# SubBoard_V1.net
KiCad netlist of a schematic drawn in EAGLE
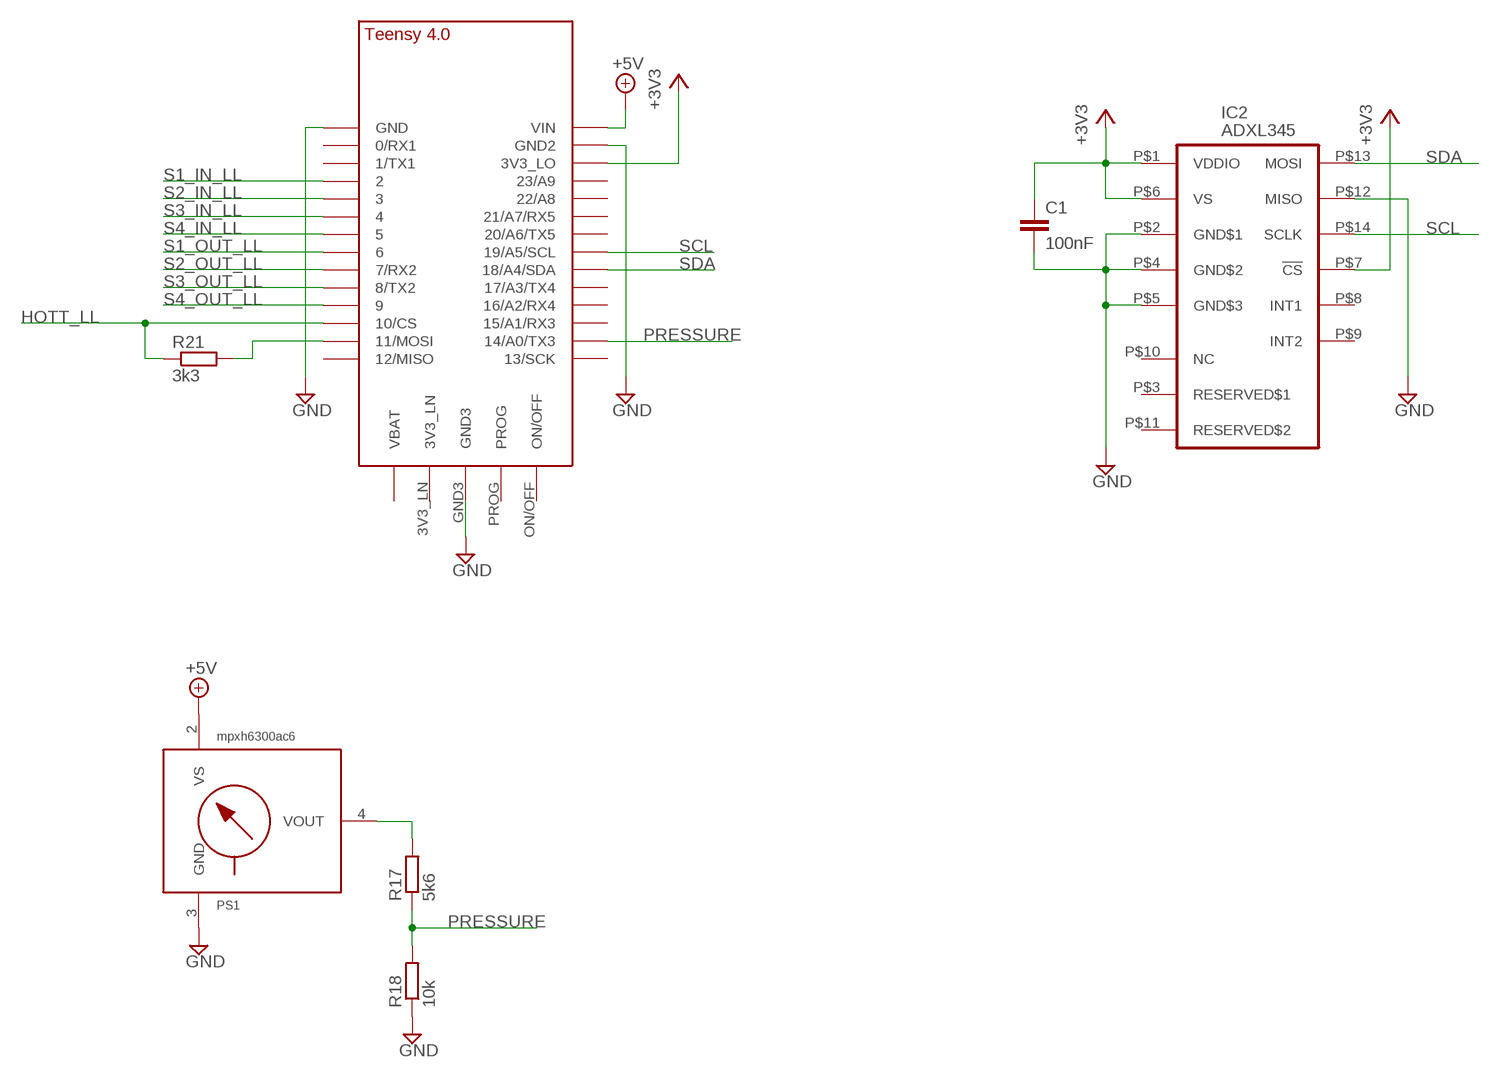
[diagram p0: schematic, sheet 1]
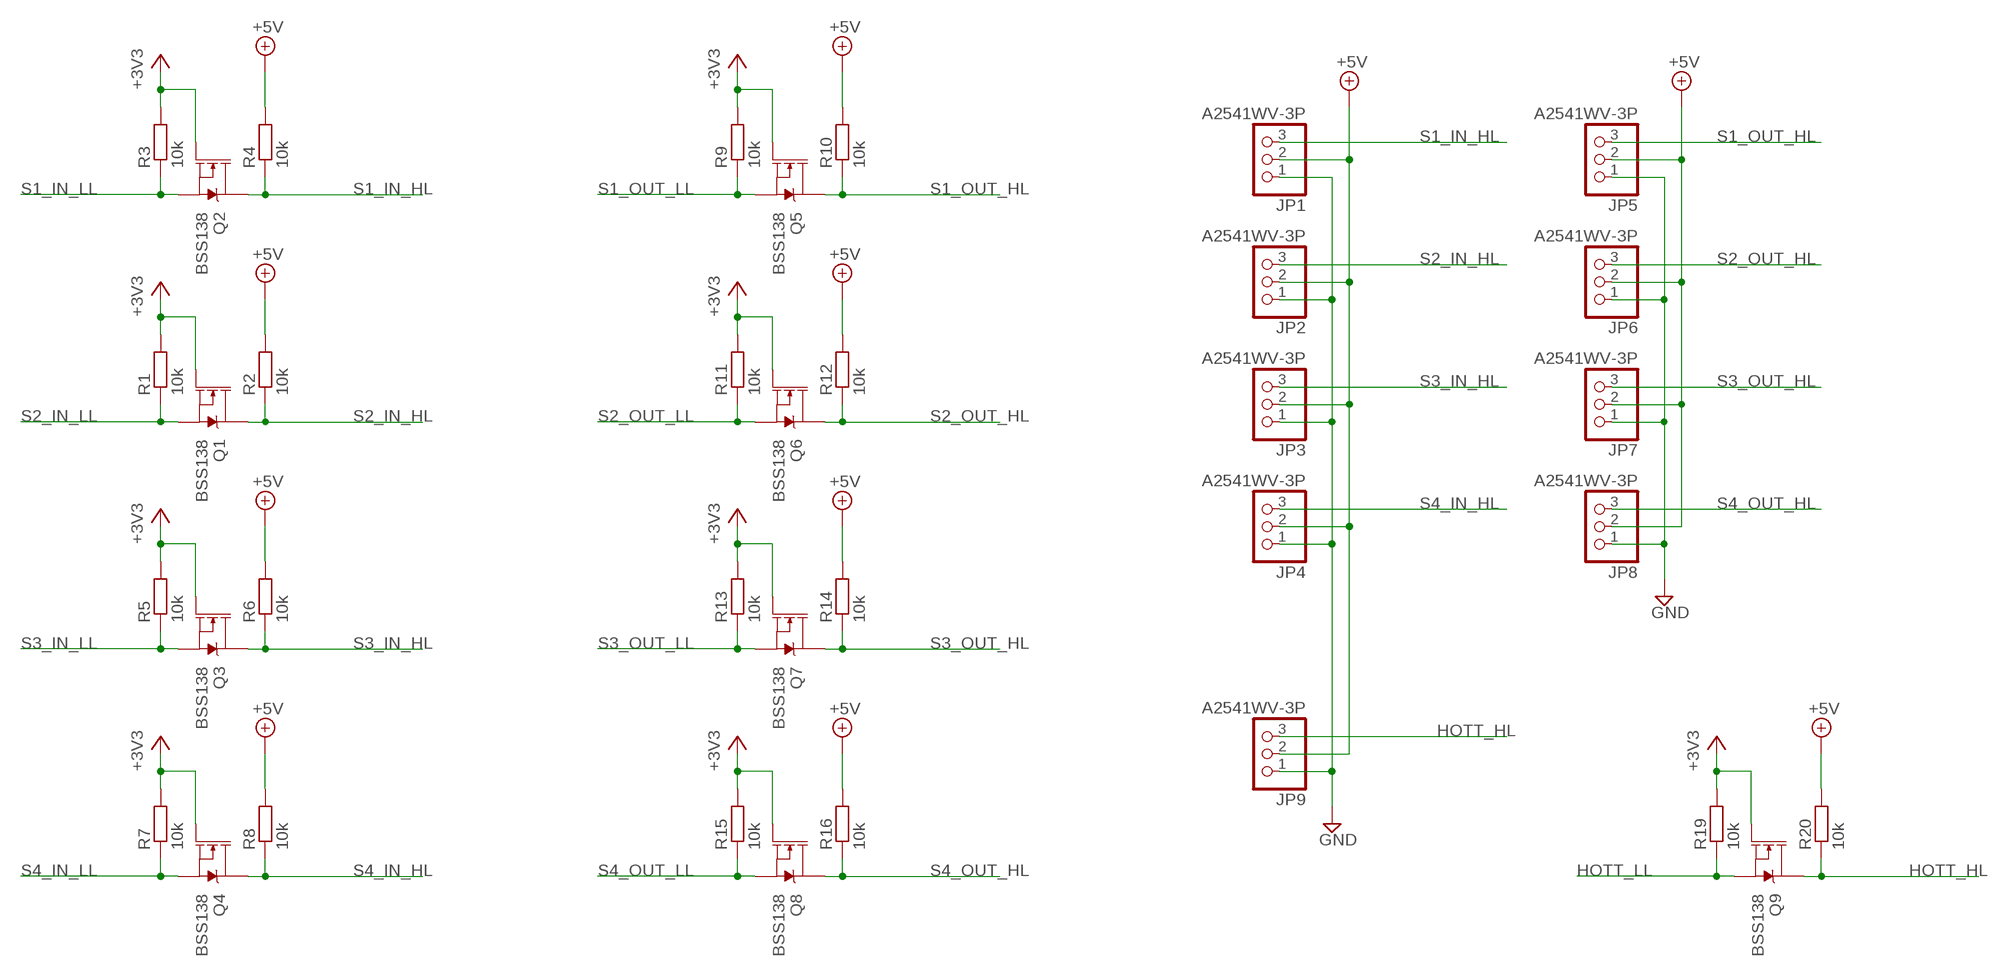
[diagram p1: schematic, sheet 2]

(export (version "E")
  (design (tool "Eeschema 10.0.6"))
  (components
    (comp (ref "C1")
      (value "100nF")
      (footprint "eagle-import:C0805")
      (libsource (lib "eagle-import") (part "C-EUC0805"))
    )
    (comp (ref "IC2")
      (value "ADXL345")
      (footprint "eagle-import:LGA14")
      (libsource (lib "eagle-import") (part "ADXL345"))
    )
    (comp (ref "M1")
      (value "TEENSY_4.0-BASIC")
      (footprint "eagle-import:TEENSY_4.0-BASIC")
      (libsource (lib "eagle-import") (part "TEENSY_4.0-BASIC"))
    )
    (comp (ref "PS1")
      (value "mpxh6300ac6")
      (footprint "eagle-import:482A")
      (libsource (lib "eagle-import") (part "MPXV5004GC6U"))
    )
    (comp (ref "R17")
      (value "5k6")
      (footprint "eagle-import:R0805")
      (libsource (lib "eagle-import") (part "R-EU_R0805"))
    )
    (comp (ref "R18")
      (value "10k")
      (footprint "eagle-import:R0805")
      (libsource (lib "eagle-import") (part "R-EU_R0805"))
    )
    (comp (ref "R21")
      (value "3k3")
      (footprint "eagle-import:R0805")
      (libsource (lib "eagle-import") (part "R-EU_R0805"))
    )
    (comp (ref "JP1")
      (value "A2541WV-3P")
      (footprint "eagle-import:1X03")
      (libsource (lib "eagle-import") (part "PINHD-1X3"))
    )
    (comp (ref "JP2")
      (value "A2541WV-3P")
      (footprint "eagle-import:1X03")
      (libsource (lib "eagle-import") (part "PINHD-1X3"))
    )
    (comp (ref "JP3")
      (value "A2541WV-3P")
      (footprint "eagle-import:1X03")
      (libsource (lib "eagle-import") (part "PINHD-1X3"))
    )
    (comp (ref "JP4")
      (value "A2541WV-3P")
      (footprint "eagle-import:1X03")
      (libsource (lib "eagle-import") (part "PINHD-1X3"))
    )
    (comp (ref "JP5")
      (value "A2541WV-3P")
      (footprint "eagle-import:1X03")
      (libsource (lib "eagle-import") (part "PINHD-1X3"))
    )
    (comp (ref "JP6")
      (value "A2541WV-3P")
      (footprint "eagle-import:1X03")
      (libsource (lib "eagle-import") (part "PINHD-1X3"))
    )
    (comp (ref "JP7")
      (value "A2541WV-3P")
      (footprint "eagle-import:1X03")
      (libsource (lib "eagle-import") (part "PINHD-1X3"))
    )
    (comp (ref "JP8")
      (value "A2541WV-3P")
      (footprint "eagle-import:1X03")
      (libsource (lib "eagle-import") (part "PINHD-1X3"))
    )
    (comp (ref "JP9")
      (value "A2541WV-3P")
      (footprint "eagle-import:1X03")
      (libsource (lib "eagle-import") (part "PINHD-1X3"))
    )
    (comp (ref "Q1")
      (value "BSS138")
      (footprint "eagle-import:SOT23-3")
      (libsource (lib "eagle-import") (part "MOSFET-NCH-BSS138"))
    )
    (comp (ref "Q2")
      (value "BSS138")
      (footprint "eagle-import:SOT23-3")
      (libsource (lib "eagle-import") (part "MOSFET-NCH-BSS138"))
    )
    (comp (ref "Q3")
      (value "BSS138")
      (footprint "eagle-import:SOT23-3")
      (libsource (lib "eagle-import") (part "MOSFET-NCH-BSS138"))
    )
    (comp (ref "Q4")
      (value "BSS138")
      (footprint "eagle-import:SOT23-3")
      (libsource (lib "eagle-import") (part "MOSFET-NCH-BSS138"))
    )
    (comp (ref "Q5")
      (value "BSS138")
      (footprint "eagle-import:SOT23-3")
      (libsource (lib "eagle-import") (part "MOSFET-NCH-BSS138"))
    )
    (comp (ref "Q6")
      (value "BSS138")
      (footprint "eagle-import:SOT23-3")
      (libsource (lib "eagle-import") (part "MOSFET-NCH-BSS138"))
    )
    (comp (ref "Q7")
      (value "BSS138")
      (footprint "eagle-import:SOT23-3")
      (libsource (lib "eagle-import") (part "MOSFET-NCH-BSS138"))
    )
    (comp (ref "Q8")
      (value "BSS138")
      (footprint "eagle-import:SOT23-3")
      (libsource (lib "eagle-import") (part "MOSFET-NCH-BSS138"))
    )
    (comp (ref "Q9")
      (value "BSS138")
      (footprint "eagle-import:SOT23-3")
      (libsource (lib "eagle-import") (part "MOSFET-NCH-BSS138"))
    )
    (comp (ref "R1")
      (value "10k")
      (footprint "eagle-import:R0603")
      (libsource (lib "eagle-import") (part "R-EU_R0603"))
    )
    (comp (ref "R2")
      (value "10k")
      (footprint "eagle-import:R0603")
      (libsource (lib "eagle-import") (part "R-EU_R0603"))
    )
    (comp (ref "R3")
      (value "10k")
      (footprint "eagle-import:R0603")
      (libsource (lib "eagle-import") (part "R-EU_R0603"))
    )
    (comp (ref "R4")
      (value "10k")
      (footprint "eagle-import:R0603")
      (libsource (lib "eagle-import") (part "R-EU_R0603"))
    )
    (comp (ref "R5")
      (value "10k")
      (footprint "eagle-import:R0603")
      (libsource (lib "eagle-import") (part "R-EU_R0603"))
    )
    (comp (ref "R6")
      (value "10k")
      (footprint "eagle-import:R0603")
      (libsource (lib "eagle-import") (part "R-EU_R0603"))
    )
    (comp (ref "R7")
      (value "10k")
      (footprint "eagle-import:R0603")
      (libsource (lib "eagle-import") (part "R-EU_R0603"))
    )
    (comp (ref "R8")
      (value "10k")
      (footprint "eagle-import:R0603")
      (libsource (lib "eagle-import") (part "R-EU_R0603"))
    )
    (comp (ref "R9")
      (value "10k")
      (footprint "eagle-import:R0603")
      (libsource (lib "eagle-import") (part "R-EU_R0603"))
    )
    (comp (ref "R10")
      (value "10k")
      (footprint "eagle-import:R0603")
      (libsource (lib "eagle-import") (part "R-EU_R0603"))
    )
    (comp (ref "R11")
      (value "10k")
      (footprint "eagle-import:R0603")
      (libsource (lib "eagle-import") (part "R-EU_R0603"))
    )
    (comp (ref "R12")
      (value "10k")
      (footprint "eagle-import:R0603")
      (libsource (lib "eagle-import") (part "R-EU_R0603"))
    )
    (comp (ref "R13")
      (value "10k")
      (footprint "eagle-import:R0603")
      (libsource (lib "eagle-import") (part "R-EU_R0603"))
    )
    (comp (ref "R14")
      (value "10k")
      (footprint "eagle-import:R0603")
      (libsource (lib "eagle-import") (part "R-EU_R0603"))
    )
    (comp (ref "R15")
      (value "10k")
      (footprint "eagle-import:R0603")
      (libsource (lib "eagle-import") (part "R-EU_R0603"))
    )
    (comp (ref "R16")
      (value "10k")
      (footprint "eagle-import:R0603")
      (libsource (lib "eagle-import") (part "R-EU_R0603"))
    )
    (comp (ref "R19")
      (value "10k")
      (footprint "eagle-import:R0603")
      (libsource (lib "eagle-import") (part "R-EU_R0603"))
    )
    (comp (ref "R20")
      (value "10k")
      (footprint "eagle-import:R0603")
      (libsource (lib "eagle-import") (part "R-EU_R0603"))
    )
  )
  (nets
    (net (code "1") (name "+3V3") (class "Default")
      (node (ref "C1") (pin "1") (pinfunction "1_1") (pintype "passive"))
      (node (ref "IC2") (pin "P$1") (pinfunction "VDDIO_P$1") (pintype "power_in"))
      (node (ref "IC2") (pin "P$6") (pinfunction "VS_P$6") (pintype "power_in"))
      (node (ref "IC2") (pin "P$7") (pinfunction "~{CS}_P$7") (pintype "input"))
      (node (ref "M1") (pin "3V3_LO") (pinfunction "3V3_LO_3V3_LO") (pintype "bidirectional"))
      (node (ref "Q1") (pin "1") (pinfunction "G_1") (pintype "bidirectional"))
      (node (ref "Q2") (pin "1") (pinfunction "G_1") (pintype "bidirectional"))
      (node (ref "Q3") (pin "1") (pinfunction "G_1") (pintype "bidirectional"))
      (node (ref "Q4") (pin "1") (pinfunction "G_1") (pintype "bidirectional"))
      (node (ref "Q5") (pin "1") (pinfunction "G_1") (pintype "bidirectional"))
      (node (ref "Q6") (pin "1") (pinfunction "G_1") (pintype "bidirectional"))
      (node (ref "Q7") (pin "1") (pinfunction "G_1") (pintype "bidirectional"))
      (node (ref "Q8") (pin "1") (pinfunction "G_1") (pintype "bidirectional"))
      (node (ref "Q9") (pin "1") (pinfunction "G_1") (pintype "bidirectional"))
      (node (ref "R1") (pin "2") (pinfunction "2_2") (pintype "passive"))
      (node (ref "R11") (pin "2") (pinfunction "2_2") (pintype "passive"))
      (node (ref "R13") (pin "2") (pinfunction "2_2") (pintype "passive"))
      (node (ref "R15") (pin "2") (pinfunction "2_2") (pintype "passive"))
      (node (ref "R19") (pin "2") (pinfunction "2_2") (pintype "passive"))
      (node (ref "R3") (pin "2") (pinfunction "2_2") (pintype "passive"))
      (node (ref "R5") (pin "2") (pinfunction "2_2") (pintype "passive"))
      (node (ref "R7") (pin "2") (pinfunction "2_2") (pintype "passive"))
      (node (ref "R9") (pin "2") (pinfunction "2_2") (pintype "passive"))
    )
    (net (code "2") (name "+5V") (class "Default")
      (node (ref "JP1") (pin "2") (pinfunction "2_2") (pintype "passive"))
      (node (ref "JP2") (pin "2") (pinfunction "2_2") (pintype "passive"))
      (node (ref "JP3") (pin "2") (pinfunction "2_2") (pintype "passive"))
      (node (ref "JP4") (pin "2") (pinfunction "2_2") (pintype "passive"))
      (node (ref "JP5") (pin "2") (pinfunction "2_2") (pintype "passive"))
      (node (ref "JP6") (pin "2") (pinfunction "2_2") (pintype "passive"))
      (node (ref "JP7") (pin "2") (pinfunction "2_2") (pintype "passive"))
      (node (ref "JP8") (pin "2") (pinfunction "2_2") (pintype "passive"))
      (node (ref "JP9") (pin "2") (pinfunction "2_2") (pintype "passive"))
      (node (ref "M1") (pin "VIN") (pinfunction "VIN_VIN") (pintype "bidirectional"))
      (node (ref "PS1") (pin "2") (pinfunction "VS_2") (pintype "power_in"))
      (node (ref "R10") (pin "2") (pinfunction "2_2") (pintype "passive"))
      (node (ref "R12") (pin "2") (pinfunction "2_2") (pintype "passive"))
      (node (ref "R14") (pin "2") (pinfunction "2_2") (pintype "passive"))
      (node (ref "R16") (pin "2") (pinfunction "2_2") (pintype "passive"))
      (node (ref "R2") (pin "2") (pinfunction "2_2") (pintype "passive"))
      (node (ref "R20") (pin "2") (pinfunction "2_2") (pintype "passive"))
      (node (ref "R4") (pin "2") (pinfunction "2_2") (pintype "passive"))
      (node (ref "R6") (pin "2") (pinfunction "2_2") (pintype "passive"))
      (node (ref "R8") (pin "2") (pinfunction "2_2") (pintype "passive"))
    )
    (net (code "3") (name "GND") (class "Default")
      (node (ref "C1") (pin "2") (pinfunction "2_2") (pintype "passive"))
      (node (ref "IC2") (pin "P$12") (pinfunction "MISO_P$12") (pintype "output"))
      (node (ref "IC2") (pin "P$2") (pinfunction "GND$1_P$2") (pintype "power_in"))
      (node (ref "IC2") (pin "P$4") (pinfunction "GND$2_P$4") (pintype "power_in"))
      (node (ref "IC2") (pin "P$5") (pinfunction "GND$3_P$5") (pintype "power_in"))
      (node (ref "JP1") (pin "1") (pinfunction "1_1") (pintype "passive"))
      (node (ref "JP2") (pin "1") (pinfunction "1_1") (pintype "passive"))
      (node (ref "JP3") (pin "1") (pinfunction "1_1") (pintype "passive"))
      (node (ref "JP4") (pin "1") (pinfunction "1_1") (pintype "passive"))
      (node (ref "JP5") (pin "1") (pinfunction "1_1") (pintype "passive"))
      (node (ref "JP6") (pin "1") (pinfunction "1_1") (pintype "passive"))
      (node (ref "JP7") (pin "1") (pinfunction "1_1") (pintype "passive"))
      (node (ref "JP8") (pin "1") (pinfunction "1_1") (pintype "passive"))
      (node (ref "JP9") (pin "1") (pinfunction "1_1") (pintype "passive"))
      (node (ref "M1") (pin "GND") (pinfunction "GND_GND") (pintype "bidirectional"))
      (node (ref "M1") (pin "GND2") (pinfunction "GND2_GND2") (pintype "bidirectional"))
      (node (ref "M1") (pin "GND3") (pinfunction "GND3_GND3") (pintype "bidirectional"))
      (node (ref "PS1") (pin "3") (pinfunction "GND_3") (pintype "power_in"))
      (node (ref "R18") (pin "1") (pinfunction "1_1") (pintype "passive"))
    )
    (net (code "4") (name "HOTT_HL") (class "Default")
      (node (ref "JP9") (pin "3") (pinfunction "3_3") (pintype "passive"))
      (node (ref "Q9") (pin "3") (pinfunction "D_3") (pintype "bidirectional"))
      (node (ref "R20") (pin "1") (pinfunction "1_1") (pintype "passive"))
    )
    (net (code "5") (name "HOTT_LL") (class "Default")
      (node (ref "M1") (pin "10/CS") (pinfunction "10/CS_10/CS") (pintype "bidirectional"))
      (node (ref "Q9") (pin "2") (pinfunction "S_2") (pintype "bidirectional"))
      (node (ref "R19") (pin "1") (pinfunction "1_1") (pintype "passive"))
      (node (ref "R21") (pin "1") (pinfunction "1_1") (pintype "passive"))
    )
    (net (code "6") (name "Net-(M1-Pad11{slash}MOSI)") (class "Default")
      (node (ref "M1") (pin "11/MOSI") (pinfunction "11/MOSI_11/MOSI") (pintype "bidirectional"))
      (node (ref "R21") (pin "2") (pinfunction "2_2") (pintype "passive"))
    )
    (net (code "7") (name "Net-(PS1-VOUT)") (class "Default")
      (node (ref "PS1") (pin "4") (pinfunction "VOUT_4") (pintype "output"))
      (node (ref "R17") (pin "2") (pinfunction "2_2") (pintype "passive"))
    )
    (net (code "8") (name "PRESSURE") (class "Default")
      (node (ref "M1") (pin "14/A0") (pinfunction "14/A0/TX3_14/A0") (pintype "bidirectional"))
      (node (ref "R17") (pin "1") (pinfunction "1_1") (pintype "passive"))
      (node (ref "R18") (pin "2") (pinfunction "2_2") (pintype "passive"))
    )
    (net (code "9") (name "S1_IN_HL") (class "Default")
      (node (ref "JP1") (pin "3") (pinfunction "3_3") (pintype "passive"))
      (node (ref "Q2") (pin "3") (pinfunction "D_3") (pintype "bidirectional"))
      (node (ref "R4") (pin "1") (pinfunction "1_1") (pintype "passive"))
    )
    (net (code "10") (name "S1_IN_LL") (class "Default")
      (node (ref "M1") (pin "2") (pinfunction "2_2") (pintype "bidirectional"))
      (node (ref "Q2") (pin "2") (pinfunction "S_2") (pintype "bidirectional"))
      (node (ref "R3") (pin "1") (pinfunction "1_1") (pintype "passive"))
    )
    (net (code "11") (name "S1_OUT_HL") (class "Default")
      (node (ref "JP5") (pin "3") (pinfunction "3_3") (pintype "passive"))
      (node (ref "Q5") (pin "3") (pinfunction "D_3") (pintype "bidirectional"))
      (node (ref "R10") (pin "1") (pinfunction "1_1") (pintype "passive"))
    )
    (net (code "12") (name "S1_OUT_LL") (class "Default")
      (node (ref "M1") (pin "6") (pinfunction "6_6") (pintype "bidirectional"))
      (node (ref "Q5") (pin "2") (pinfunction "S_2") (pintype "bidirectional"))
      (node (ref "R9") (pin "1") (pinfunction "1_1") (pintype "passive"))
    )
    (net (code "13") (name "S2_IN_HL") (class "Default")
      (node (ref "JP2") (pin "3") (pinfunction "3_3") (pintype "passive"))
      (node (ref "Q1") (pin "3") (pinfunction "D_3") (pintype "bidirectional"))
      (node (ref "R2") (pin "1") (pinfunction "1_1") (pintype "passive"))
    )
    (net (code "14") (name "S2_IN_LL") (class "Default")
      (node (ref "M1") (pin "3/CANTX") (pinfunction "3_3/CANTX") (pintype "bidirectional"))
      (node (ref "Q1") (pin "2") (pinfunction "S_2") (pintype "bidirectional"))
      (node (ref "R1") (pin "1") (pinfunction "1_1") (pintype "passive"))
    )
    (net (code "15") (name "S2_OUT_HL") (class "Default")
      (node (ref "JP6") (pin "3") (pinfunction "3_3") (pintype "passive"))
      (node (ref "Q6") (pin "3") (pinfunction "D_3") (pintype "bidirectional"))
      (node (ref "R12") (pin "1") (pinfunction "1_1") (pintype "passive"))
    )
    (net (code "16") (name "S2_OUT_LL") (class "Default")
      (node (ref "M1") (pin "7") (pinfunction "7/RX2_7") (pintype "bidirectional"))
      (node (ref "Q6") (pin "2") (pinfunction "S_2") (pintype "bidirectional"))
      (node (ref "R11") (pin "1") (pinfunction "1_1") (pintype "passive"))
    )
    (net (code "17") (name "S3_IN_HL") (class "Default")
      (node (ref "JP3") (pin "3") (pinfunction "3_3") (pintype "passive"))
      (node (ref "Q3") (pin "3") (pinfunction "D_3") (pintype "bidirectional"))
      (node (ref "R6") (pin "1") (pinfunction "1_1") (pintype "passive"))
    )
    (net (code "18") (name "S3_IN_LL") (class "Default")
      (node (ref "M1") (pin "4/CANRX") (pinfunction "4_4/CANRX") (pintype "bidirectional"))
      (node (ref "Q3") (pin "2") (pinfunction "S_2") (pintype "bidirectional"))
      (node (ref "R5") (pin "1") (pinfunction "1_1") (pintype "passive"))
    )
    (net (code "19") (name "S3_OUT_HL") (class "Default")
      (node (ref "JP7") (pin "3") (pinfunction "3_3") (pintype "passive"))
      (node (ref "Q7") (pin "3") (pinfunction "D_3") (pintype "bidirectional"))
      (node (ref "R14") (pin "1") (pinfunction "1_1") (pintype "passive"))
    )
    (net (code "20") (name "S3_OUT_LL") (class "Default")
      (node (ref "M1") (pin "8") (pinfunction "8/TX2_8") (pintype "bidirectional"))
      (node (ref "Q7") (pin "2") (pinfunction "S_2") (pintype "bidirectional"))
      (node (ref "R13") (pin "1") (pinfunction "1_1") (pintype "passive"))
    )
    (net (code "21") (name "S4_IN_HL") (class "Default")
      (node (ref "JP4") (pin "3") (pinfunction "3_3") (pintype "passive"))
      (node (ref "Q4") (pin "3") (pinfunction "D_3") (pintype "bidirectional"))
      (node (ref "R8") (pin "1") (pinfunction "1_1") (pintype "passive"))
    )
    (net (code "22") (name "S4_IN_LL") (class "Default")
      (node (ref "M1") (pin "5") (pinfunction "5_5") (pintype "bidirectional"))
      (node (ref "Q4") (pin "2") (pinfunction "S_2") (pintype "bidirectional"))
      (node (ref "R7") (pin "1") (pinfunction "1_1") (pintype "passive"))
    )
    (net (code "23") (name "S4_OUT_HL") (class "Default")
      (node (ref "JP8") (pin "3") (pinfunction "3_3") (pintype "passive"))
      (node (ref "Q8") (pin "3") (pinfunction "D_3") (pintype "bidirectional"))
      (node (ref "R16") (pin "1") (pinfunction "1_1") (pintype "passive"))
    )
    (net (code "24") (name "S4_OUT_LL") (class "Default")
      (node (ref "M1") (pin "9/CS") (pinfunction "9_9/CS") (pintype "bidirectional"))
      (node (ref "Q8") (pin "2") (pinfunction "S_2") (pintype "bidirectional"))
      (node (ref "R15") (pin "1") (pinfunction "1_1") (pintype "passive"))
    )
    (net (code "25") (name "SCL") (class "Default")
      (node (ref "IC2") (pin "P$14") (pinfunction "SCLK_P$14") (pintype "input"))
      (node (ref "M1") (pin "19/A5/SCL") (pinfunction "19/A5/SCL_19/A5/SCL") (pintype "bidirectional"))
    )
    (net (code "26") (name "SDA") (class "Default")
      (node (ref "IC2") (pin "P$13") (pinfunction "MOSI_P$13") (pintype "input"))
      (node (ref "M1") (pin "18/A4/SDA") (pinfunction "18/A4/SDA_18/A4/SDA") (pintype "bidirectional"))
    )
    (net (code "27") (name "unconnected-(IC2-INT1-PadP$8)") (class "Default")
      (node (ref "IC2") (pin "P$8") (pinfunction "INT1_P$8") (pintype "output"))
    )
    (net (code "28") (name "unconnected-(IC2-INT2-PadP$9)") (class "Default")
      (node (ref "IC2") (pin "P$9") (pinfunction "INT2_P$9") (pintype "output"))
    )
    (net (code "29") (name "unconnected-(IC2-NC-PadP$10)") (class "Default")
      (node (ref "IC2") (pin "P$10") (pinfunction "NC_P$10") (pintype "bidirectional"))
    )
    (net (code "30") (name "unconnected-(IC2-RESERVED$1-PadP$3)") (class "Default")
      (node (ref "IC2") (pin "P$3") (pinfunction "RESERVED$1_P$3") (pintype "bidirectional"))
    )
    (net (code "31") (name "unconnected-(IC2-RESERVED$2-PadP$11)") (class "Default")
      (node (ref "IC2") (pin "P$11") (pinfunction "RESERVED$2_P$11") (pintype "bidirectional"))
    )
    (net (code "32") (name "unconnected-(M1-0{slash}RX1-Pad0{slash}RX)") (class "Default")
      (node (ref "M1") (pin "0/RX") (pinfunction "0/RX1_0/RX") (pintype "bidirectional"))
    )
    (net (code "33") (name "unconnected-(M1-1{slash}TX1-Pad1{slash}TX)") (class "Default")
      (node (ref "M1") (pin "1/TX") (pinfunction "1/TX1_1/TX") (pintype "bidirectional"))
    )
    (net (code "34") (name "unconnected-(M1-15{slash}A1{slash}RX3-Pad15{slash}A1)") (class "Default")
      (node (ref "M1") (pin "15/A1") (pinfunction "15/A1/RX3_15/A1") (pintype "bidirectional"))
    )
    (net (code "35") (name "unconnected-(M1-16{slash}A2{slash}RX4-Pad16{slash}A2)") (class "Default")
      (node (ref "M1") (pin "16/A2") (pinfunction "16/A2/RX4_16/A2") (pintype "bidirectional"))
    )
    (net (code "36") (name "unconnected-(M1-17{slash}A3{slash}TX4-Pad17{slash}A3)") (class "Default")
      (node (ref "M1") (pin "17/A3") (pinfunction "17/A3/TX4_17/A3") (pintype "bidirectional"))
    )
    (net (code "37") (name "unconnected-(M1-20{slash}A6{slash}TX5-Pad20{slash}A6)") (class "Default")
      (node (ref "M1") (pin "20/A6") (pinfunction "20/A6/TX5_20/A6") (pintype "bidirectional"))
    )
    (net (code "38") (name "unconnected-(M1-21{slash}A7{slash}RX5-Pad21{slash}A7)") (class "Default")
      (node (ref "M1") (pin "21/A7") (pinfunction "21/A7/RX5_21/A7") (pintype "bidirectional"))
    )
    (net (code "39") (name "unconnected-(M1-Pad3V3_LN)") (class "Default")
      (node (ref "M1") (pin "3V3_LN") (pinfunction "3V3_LN_3V3_LN") (pintype "bidirectional"))
    )
    (net (code "40") (name "unconnected-(M1-Pad12{slash}MISO)") (class "Default")
      (node (ref "M1") (pin "12/MISO") (pinfunction "12/MISO_12/MISO") (pintype "bidirectional"))
    )
    (net (code "41") (name "unconnected-(M1-Pad13{slash}SCK)") (class "Default")
      (node (ref "M1") (pin "13/SCK") (pinfunction "13/SCK_13/SCK") (pintype "bidirectional"))
    )
    (net (code "42") (name "unconnected-(M1-Pad22{slash}A8)") (class "Default")
      (node (ref "M1") (pin "22/A8") (pinfunction "22/A8_22/A8") (pintype "bidirectional"))
    )
    (net (code "43") (name "unconnected-(M1-Pad23{slash}A9)") (class "Default")
      (node (ref "M1") (pin "23/A9") (pinfunction "23/A9_23/A9") (pintype "bidirectional"))
    )
    (net (code "44") (name "unconnected-(M1-PadON{slash}OFF)") (class "Default")
      (node (ref "M1") (pin "ON/OFF") (pinfunction "ON/OFF_ON/OFF") (pintype "bidirectional"))
    )
    (net (code "45") (name "unconnected-(M1-PadPROG)") (class "Default")
      (node (ref "M1") (pin "PROG") (pinfunction "PROG_PROG") (pintype "bidirectional"))
    )
    (net (code "46") (name "unconnected-(M1-VBAT-PadVBAT\\)") (class "Default")
      (node (ref "M1") (pin "VBAT\\") (pinfunction "VBAT_VBAT\\") (pintype "bidirectional"))
    )
    (net (code "47") (name "unconnected-(PS1-NC-Pad1)") (class "Default")
      (node (ref "PS1") (pin "1") (pinfunction "NC_1") (pintype "no_connect"))
    )
    (net (code "48") (name "unconnected-(PS1-NC-Pad5)") (class "Default")
      (node (ref "PS1") (pin "5") (pinfunction "NC_5") (pintype "no_connect"))
    )
    (net (code "49") (name "unconnected-(PS1-NC-Pad6)") (class "Default")
      (node (ref "PS1") (pin "6") (pinfunction "NC_6") (pintype "no_connect"))
    )
  )
)
